# injector.net
KiCad netlist of a schematic drawn in EAGLE
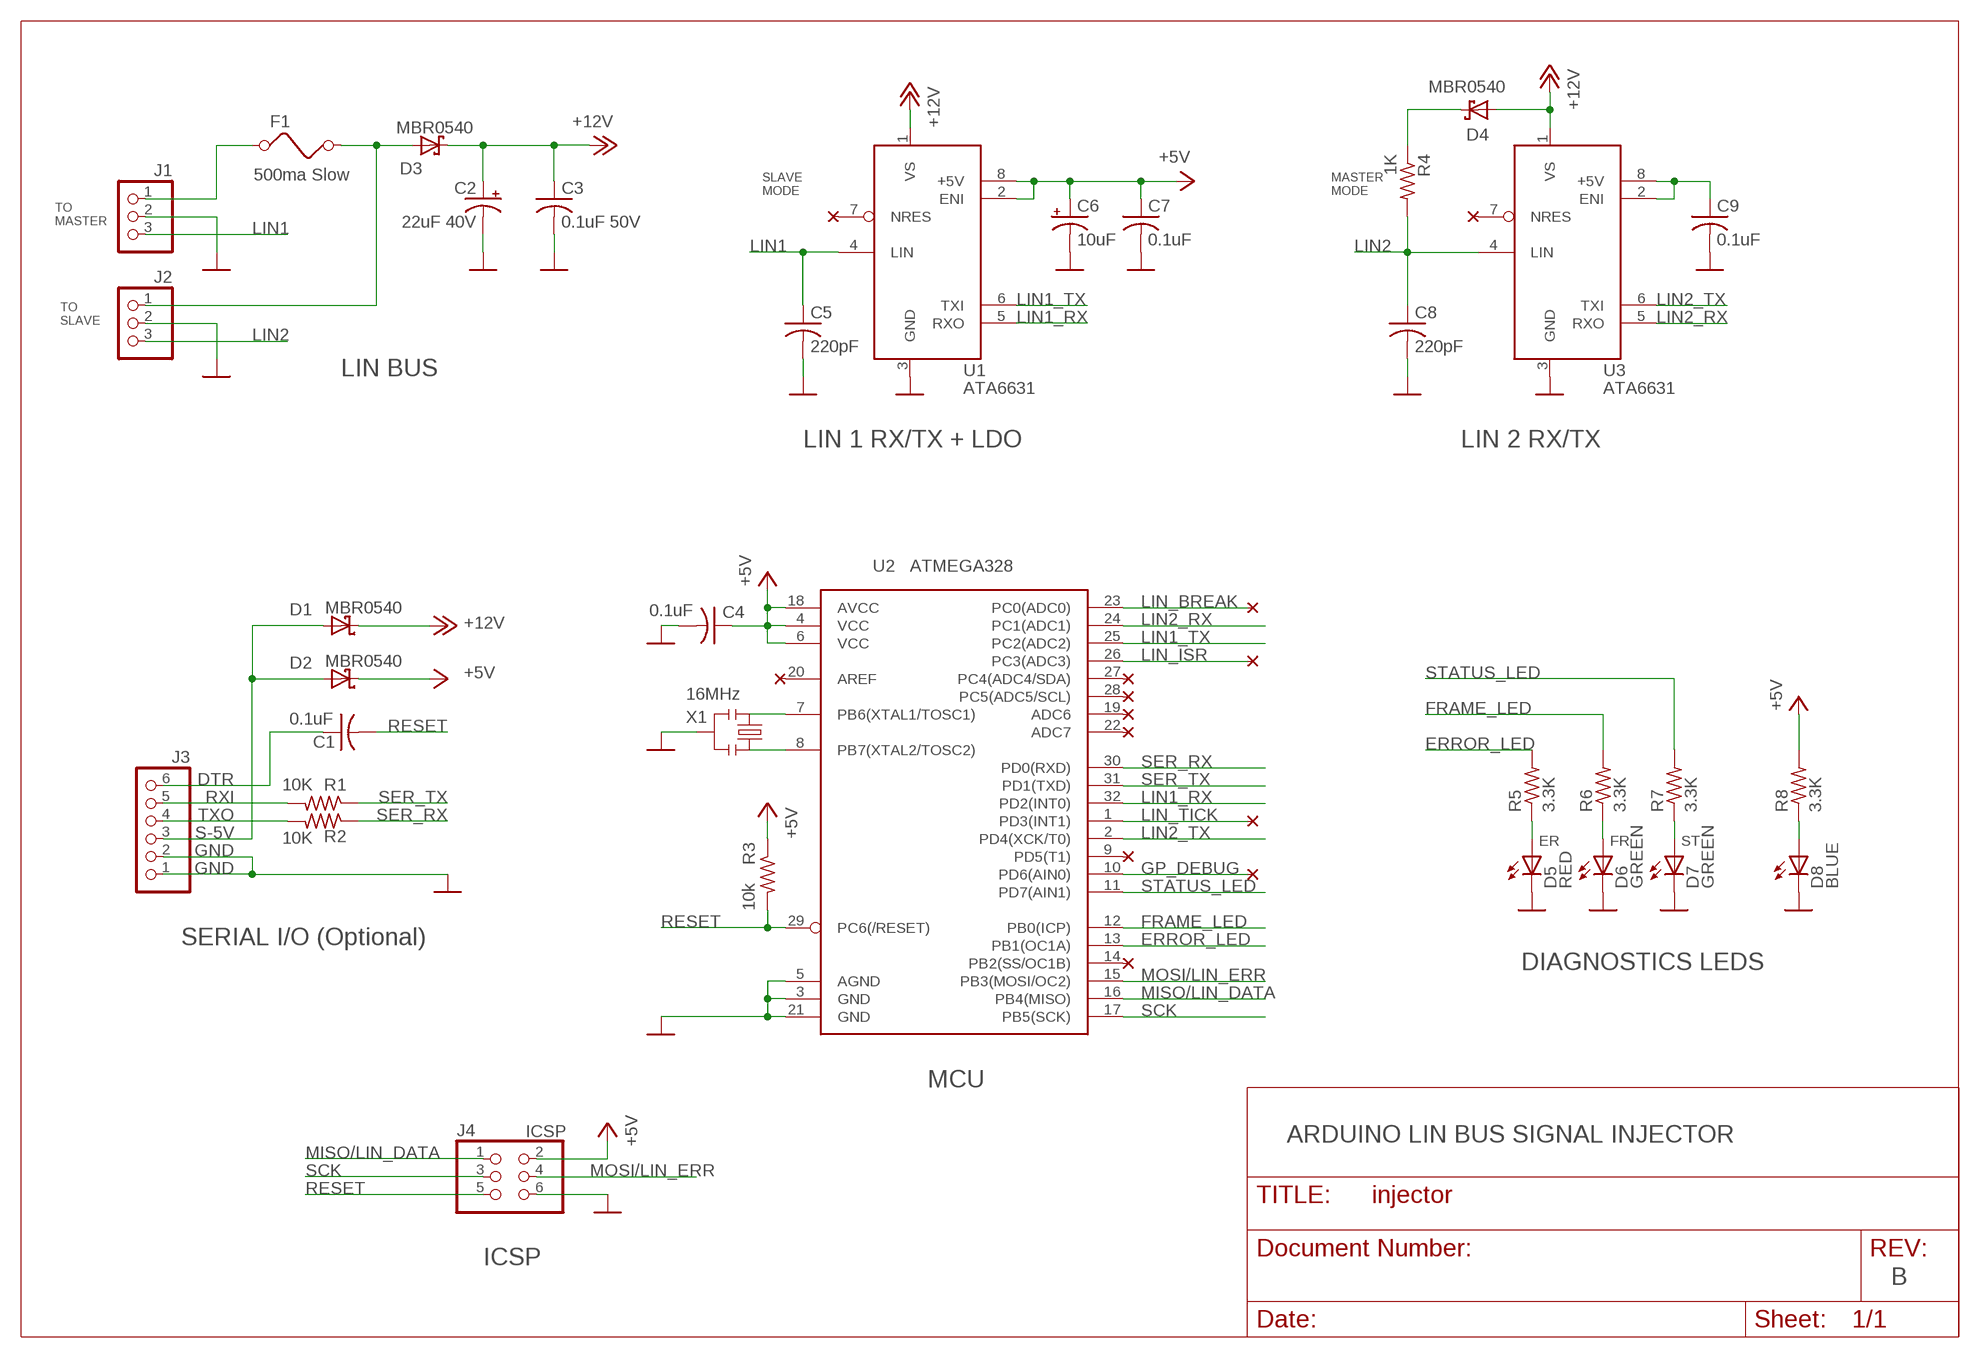
[diagram p0: schematic, sheet 1]

(export (version "E")
  (design (tool "Eeschema 10.0.6"))
  (components
    (comp (ref "C1")
      (value "0.1uF")
      (footprint "eagle-import:C0805")
      (libsource (lib "eagle-import") (part "C-USC0805"))
    )
    (comp (ref "C2")
      (value "22uF 40V")
      (footprint "eagle-import:UD-6,3X5,8_NICHICON")
      (libsource (lib "eagle-import") (part "CPOL-USUD-6,3X5,8"))
    )
    (comp (ref "C3")
      (value "0.1uF 50V")
      (footprint "eagle-import:C0805")
      (libsource (lib "eagle-import") (part "C-USC0805"))
    )
    (comp (ref "C4")
      (value "0.1uF")
      (footprint "eagle-import:C0805")
      (libsource (lib "eagle-import") (part "C-USC0805"))
    )
    (comp (ref "C5")
      (value "220pF")
      (footprint "eagle-import:C0805")
      (libsource (lib "eagle-import") (part "C-USC0805"))
    )
    (comp (ref "C6")
      (value "10uF")
      (footprint "eagle-import:A_3216-18R")
      (libsource (lib "eagle-import") (part "CPOL-USA/3216-18R"))
    )
    (comp (ref "C7")
      (value "0.1uF")
      (footprint "eagle-import:C0805")
      (libsource (lib "eagle-import") (part "C-USC0805"))
    )
    (comp (ref "C8")
      (value "220pF")
      (footprint "eagle-import:C0805")
      (libsource (lib "eagle-import") (part "C-USC0805"))
    )
    (comp (ref "C9")
      (value "0.1uF")
      (footprint "eagle-import:C0805")
      (libsource (lib "eagle-import") (part "C-USC0805"))
    )
    (comp (ref "D1")
      (value "MBR0540")
      (footprint "eagle-import:SOD123FL")
      (libsource (lib "eagle-import") (part "SMF5.0AT1"))
    )
    (comp (ref "D2")
      (value "MBR0540")
      (footprint "eagle-import:SOD123FL")
      (libsource (lib "eagle-import") (part "SMF5.0AT1"))
    )
    (comp (ref "D3")
      (value "MBR0540")
      (footprint "eagle-import:SOD123FL")
      (libsource (lib "eagle-import") (part "SMF5.0AT1"))
    )
    (comp (ref "D4")
      (value "MBR0540")
      (footprint "eagle-import:SOD123FL")
      (libsource (lib "eagle-import") (part "SMF5.0AT1"))
    )
    (comp (ref "D5")
      (value "RED")
      (footprint "eagle-import:1206-LED")
      (libsource (lib "eagle-import") (part "LED"))
    )
    (comp (ref "D6")
      (value "GREEN")
      (footprint "eagle-import:1206-LED")
      (libsource (lib "eagle-import") (part "LED"))
    )
    (comp (ref "D7")
      (value "GREEN")
      (footprint "eagle-import:1206-LED")
      (libsource (lib "eagle-import") (part "LED"))
    )
    (comp (ref "D8")
      (value "BLUE")
      (footprint "eagle-import:1206-LED")
      (libsource (lib "eagle-import") (part "LED"))
    )
    (comp (ref "F1")
      (value "500ma Slow")
      (footprint "eagle-import:1206")
      (libsource (lib "eagle-import") (part "FUSE"))
    )
    (comp (ref "J1")
      (value "PINHD-1X3")
      (footprint "eagle-import:1X03")
      (libsource (lib "eagle-import") (part "PINHD-1X3"))
    )
    (comp (ref "J2")
      (value "PINHD-1X3")
      (footprint "eagle-import:1X03")
      (libsource (lib "eagle-import") (part "PINHD-1X3"))
    )
    (comp (ref "J3")
      (value "PINHD-1X6")
      (footprint "eagle-import:1X06")
      (libsource (lib "eagle-import") (part "PINHD-1X6"))
    )
    (comp (ref "J4")
      (value "ICSP")
      (footprint "eagle-import:2X03")
      (libsource (lib "eagle-import") (part "PINHD-2X3"))
    )
    (comp (ref "R1")
      (value "10K")
      (footprint "eagle-import:R0805")
      (libsource (lib "eagle-import") (part "R-US_R0805"))
    )
    (comp (ref "R2")
      (value "10K")
      (footprint "eagle-import:R0805")
      (libsource (lib "eagle-import") (part "R-US_R0805"))
    )
    (comp (ref "R3")
      (value "10k")
      (footprint "eagle-import:R0805")
      (libsource (lib "eagle-import") (part "R-US_R0805"))
    )
    (comp (ref "R4")
      (value "1K")
      (footprint "eagle-import:R0805")
      (libsource (lib "eagle-import") (part "R-US_R0805"))
    )
    (comp (ref "R5")
      (value "3.3K")
      (footprint "eagle-import:R0805")
      (libsource (lib "eagle-import") (part "R-US_R0805"))
    )
    (comp (ref "R6")
      (value "3.3K")
      (footprint "eagle-import:R0805")
      (libsource (lib "eagle-import") (part "R-US_R0805"))
    )
    (comp (ref "R7")
      (value "3.3K")
      (footprint "eagle-import:R0805")
      (libsource (lib "eagle-import") (part "R-US_R0805"))
    )
    (comp (ref "R8")
      (value "3.3K")
      (footprint "eagle-import:R0805")
      (libsource (lib "eagle-import") (part "R-US_R0805"))
    )
    (comp (ref "U1")
      (value "ATA6631")
      (footprint "eagle-import:SO-08")
      (libsource (lib "eagle-import") (part "ATA6631"))
    )
    (comp (ref "U2")
      (value "ATMEGA328")
      (footprint "eagle-import:TQFP32-08")
      (libsource (lib "eagle-import") (part "ATMEGA328"))
    )
    (comp (ref "U3")
      (value "ATA6631")
      (footprint "eagle-import:SO-08")
      (libsource (lib "eagle-import") (part "ATA6631"))
    )
    (comp (ref "X1")
      (value "16MHz")
      (footprint "eagle-import:RESONATOR-SMD")
      (libsource (lib "eagle-import") (part "RESONATORSMD"))
    )
  )
  (nets
    (net (code "1") (name "+5V") (class "Default")
      (node (ref "C4") (pin "1") (pinfunction "1_1") (pintype "passive"))
      (node (ref "C6") (pin "+") (pinfunction "+_+") (pintype "passive"))
      (node (ref "C7") (pin "1") (pinfunction "1_1") (pintype "passive"))
      (node (ref "D2") (pin "C") (pinfunction "C_C") (pintype "passive"))
      (node (ref "J4") (pin "2") (pinfunction "2_2") (pintype "passive"))
      (node (ref "R3") (pin "1") (pinfunction "1_1") (pintype "passive"))
      (node (ref "R8") (pin "2") (pinfunction "2_2") (pintype "passive"))
      (node (ref "U1") (pin "2") (pinfunction "ENI_2") (pintype "input"))
      (node (ref "U1") (pin "8") (pinfunction "+5V_8") (pintype "power_in"))
      (node (ref "U2") (pin "18") (pinfunction "AVCC_18") (pintype "power_in"))
      (node (ref "U2") (pin "4") (pinfunction "VCC_4") (pintype "power_in"))
      (node (ref "U2") (pin "6") (pinfunction "VCC_6") (pintype "power_in"))
    )
    (net (code "2") (name "+12V") (class "Default")
      (node (ref "C2") (pin "+") (pinfunction "+_+") (pintype "passive"))
      (node (ref "C3") (pin "1") (pinfunction "1_1") (pintype "passive"))
      (node (ref "D1") (pin "C") (pinfunction "C_C") (pintype "passive"))
      (node (ref "D3") (pin "C") (pinfunction "C_C") (pintype "passive"))
      (node (ref "D4") (pin "A") (pinfunction "A_A") (pintype "passive"))
      (node (ref "U1") (pin "1") (pinfunction "VS_1") (pintype "power_in"))
      (node (ref "U3") (pin "1") (pinfunction "VS_1") (pintype "power_in"))
    )
    (net (code "3") (name "/AREF") (class "Default")
      (node (ref "U2") (pin "20") (pinfunction "AREF_20") (pintype "power_in"))
    )
    (net (code "4") (name "/DTR") (class "Default")
      (node (ref "C1") (pin "1") (pinfunction "1_1") (pintype "passive"))
      (node (ref "J3") (pin "6") (pinfunction "6_6") (pintype "passive"))
    )
    (net (code "5") (name "/ERROR_LED") (class "Default")
      (node (ref "R5") (pin "2") (pinfunction "2_2") (pintype "passive"))
      (node (ref "U2") (pin "13") (pinfunction "PB1(OC1A)_13") (pintype "bidirectional"))
    )
    (net (code "6") (name "/FRAME_LED") (class "Default")
      (node (ref "R6") (pin "2") (pinfunction "2_2") (pintype "passive"))
      (node (ref "U2") (pin "12") (pinfunction "PB0(ICP)_12") (pintype "bidirectional"))
    )
    (net (code "7") (name "/GP_DEBUG") (class "Default")
      (node (ref "U2") (pin "10") (pinfunction "PD6(AIN0)_10") (pintype "bidirectional"))
    )
    (net (code "8") (name "/LIN1") (class "Default")
      (node (ref "C5") (pin "1") (pinfunction "1_1") (pintype "passive"))
      (node (ref "J1") (pin "3") (pinfunction "3_3") (pintype "passive"))
      (node (ref "U1") (pin "4") (pinfunction "LIN_4") (pintype "bidirectional"))
    )
    (net (code "9") (name "/LIN1_RX") (class "Default")
      (node (ref "U1") (pin "5") (pinfunction "RXO_5") (pintype "output"))
      (node (ref "U2") (pin "32") (pinfunction "PD2(INT0)_32") (pintype "bidirectional"))
    )
    (net (code "10") (name "/LIN1_TX") (class "Default")
      (node (ref "U1") (pin "6") (pinfunction "TXI_6") (pintype "input"))
      (node (ref "U2") (pin "25") (pinfunction "PC2(ADC2)_25") (pintype "bidirectional"))
    )
    (net (code "11") (name "/LIN2") (class "Default")
      (node (ref "C8") (pin "1") (pinfunction "1_1") (pintype "passive"))
      (node (ref "J2") (pin "3") (pinfunction "3_3") (pintype "passive"))
      (node (ref "R4") (pin "2") (pinfunction "2_2") (pintype "passive"))
      (node (ref "U3") (pin "4") (pinfunction "LIN_4") (pintype "bidirectional"))
    )
    (net (code "12") (name "/LIN2_RX") (class "Default")
      (node (ref "U2") (pin "24") (pinfunction "PC1(ADC1)_24") (pintype "bidirectional"))
      (node (ref "U3") (pin "5") (pinfunction "RXO_5") (pintype "output"))
    )
    (net (code "13") (name "/LIN2_TX") (class "Default")
      (node (ref "U2") (pin "2") (pinfunction "PD4(XCK/T0)_2") (pintype "bidirectional"))
      (node (ref "U3") (pin "6") (pinfunction "TXI_6") (pintype "input"))
    )
    (net (code "14") (name "/LIN_BREAK") (class "Default")
      (node (ref "U2") (pin "23") (pinfunction "PC0(ADC0)_23") (pintype "bidirectional"))
    )
    (net (code "15") (name "/LIN_ISR") (class "Default")
      (node (ref "U2") (pin "26") (pinfunction "PC3(ADC3)_26") (pintype "bidirectional"))
    )
    (net (code "16") (name "/LIN_TICK") (class "Default")
      (node (ref "U2") (pin "1") (pinfunction "PD3(INT1)_1") (pintype "bidirectional"))
    )
    (net (code "17") (name "/MISO{slash}LIN_DATA") (class "Default")
      (node (ref "J4") (pin "1") (pinfunction "1_1") (pintype "passive"))
      (node (ref "U2") (pin "16") (pinfunction "PB4(MISO)_16") (pintype "bidirectional"))
    )
    (net (code "18") (name "/MOSI{slash}LIN_ERR") (class "Default")
      (node (ref "J4") (pin "4") (pinfunction "4_4") (pintype "passive"))
      (node (ref "U2") (pin "15") (pinfunction "PB3(MOSI/OC2)_15") (pintype "bidirectional"))
    )
    (net (code "19") (name "/RESET") (class "Default")
      (node (ref "C1") (pin "2") (pinfunction "2_2") (pintype "passive"))
      (node (ref "J4") (pin "5") (pinfunction "5_5") (pintype "passive"))
      (node (ref "R3") (pin "2") (pinfunction "2_2") (pintype "passive"))
      (node (ref "U2") (pin "29") (pinfunction "PC6(/RESET)_29") (pintype "bidirectional"))
    )
    (net (code "20") (name "/RXI") (class "Default")
      (node (ref "J3") (pin "5") (pinfunction "5_5") (pintype "passive"))
      (node (ref "R1") (pin "2") (pinfunction "2_2") (pintype "passive"))
    )
    (net (code "21") (name "/S-5V") (class "Default")
      (node (ref "D1") (pin "A") (pinfunction "A_A") (pintype "passive"))
      (node (ref "D2") (pin "A") (pinfunction "A_A") (pintype "passive"))
      (node (ref "J3") (pin "3") (pinfunction "3_3") (pintype "passive"))
    )
    (net (code "22") (name "/SCK") (class "Default")
      (node (ref "J4") (pin "3") (pinfunction "3_3") (pintype "passive"))
      (node (ref "U2") (pin "17") (pinfunction "PB5(SCK)_17") (pintype "bidirectional"))
    )
    (net (code "23") (name "/SER_RX") (class "Default")
      (node (ref "R2") (pin "1") (pinfunction "1_1") (pintype "passive"))
      (node (ref "U2") (pin "30") (pinfunction "PD0(RXD)_30") (pintype "bidirectional"))
    )
    (net (code "24") (name "/SER_TX") (class "Default")
      (node (ref "R1") (pin "1") (pinfunction "1_1") (pintype "passive"))
      (node (ref "U2") (pin "31") (pinfunction "PD1(TXD)_31") (pintype "bidirectional"))
    )
    (net (code "25") (name "/STATUS_LED") (class "Default")
      (node (ref "R7") (pin "2") (pinfunction "2_2") (pintype "passive"))
      (node (ref "U2") (pin "11") (pinfunction "PD7(AIN1)_11") (pintype "bidirectional"))
    )
    (net (code "26") (name "/TXO") (class "Default")
      (node (ref "J3") (pin "4") (pinfunction "4_4") (pintype "passive"))
      (node (ref "R2") (pin "2") (pinfunction "2_2") (pintype "passive"))
    )
    (net (code "27") (name "GND") (class "Default")
      (node (ref "C2") (pin "-") (pinfunction "-_-") (pintype "passive"))
      (node (ref "C3") (pin "2") (pinfunction "2_2") (pintype "passive"))
      (node (ref "C4") (pin "2") (pinfunction "2_2") (pintype "passive"))
      (node (ref "C5") (pin "2") (pinfunction "2_2") (pintype "passive"))
      (node (ref "C6") (pin "-") (pinfunction "-_-") (pintype "passive"))
      (node (ref "C7") (pin "2") (pinfunction "2_2") (pintype "passive"))
      (node (ref "C8") (pin "2") (pinfunction "2_2") (pintype "passive"))
      (node (ref "C9") (pin "2") (pinfunction "2_2") (pintype "passive"))
      (node (ref "D5") (pin "C") (pinfunction "C_C") (pintype "passive"))
      (node (ref "D6") (pin "C") (pinfunction "C_C") (pintype "passive"))
      (node (ref "D7") (pin "C") (pinfunction "C_C") (pintype "passive"))
      (node (ref "D8") (pin "C") (pinfunction "C_C") (pintype "passive"))
      (node (ref "J1") (pin "2") (pinfunction "2_2") (pintype "passive"))
      (node (ref "J2") (pin "2") (pinfunction "2_2") (pintype "passive"))
      (node (ref "J3") (pin "1") (pinfunction "1_1") (pintype "passive"))
      (node (ref "J3") (pin "2") (pinfunction "2_2") (pintype "passive"))
      (node (ref "J4") (pin "6") (pinfunction "6_6") (pintype "passive"))
      (node (ref "U1") (pin "3") (pinfunction "GND_3") (pintype "power_in"))
      (node (ref "U2") (pin "21") (pinfunction "GND_21") (pintype "power_in"))
      (node (ref "U2") (pin "3") (pinfunction "GND_3") (pintype "power_in"))
      (node (ref "U2") (pin "5") (pinfunction "AGND_5") (pintype "power_in"))
      (node (ref "U3") (pin "3") (pinfunction "GND_3") (pintype "power_in"))
      (node (ref "X1") (pin "2") (pinfunction "2_2") (pintype "passive"))
    )
    (net (code "28") (name "Net-(D3-PadA)") (class "Default")
      (node (ref "D3") (pin "A") (pinfunction "A_A") (pintype "passive"))
      (node (ref "F1") (pin "2") (pinfunction "2_2") (pintype "passive"))
      (node (ref "J2") (pin "1") (pinfunction "1_1") (pintype "passive"))
    )
    (net (code "29") (name "Net-(D4-PadC)") (class "Default")
      (node (ref "D4") (pin "C") (pinfunction "C_C") (pintype "passive"))
      (node (ref "R4") (pin "1") (pinfunction "1_1") (pintype "passive"))
    )
    (net (code "30") (name "Net-(D5-PadA)") (class "Default")
      (node (ref "D5") (pin "A") (pinfunction "A_A") (pintype "passive"))
      (node (ref "R5") (pin "1") (pinfunction "1_1") (pintype "passive"))
    )
    (net (code "31") (name "Net-(D6-PadA)") (class "Default")
      (node (ref "D6") (pin "A") (pinfunction "A_A") (pintype "passive"))
      (node (ref "R6") (pin "1") (pinfunction "1_1") (pintype "passive"))
    )
    (net (code "32") (name "Net-(D7-PadA)") (class "Default")
      (node (ref "D7") (pin "A") (pinfunction "A_A") (pintype "passive"))
      (node (ref "R7") (pin "1") (pinfunction "1_1") (pintype "passive"))
    )
    (net (code "33") (name "Net-(D8-PadA)") (class "Default")
      (node (ref "D8") (pin "A") (pinfunction "A_A") (pintype "passive"))
      (node (ref "R8") (pin "1") (pinfunction "1_1") (pintype "passive"))
    )
    (net (code "34") (name "Net-(F1-Pad1)") (class "Default")
      (node (ref "F1") (pin "1") (pinfunction "1_1") (pintype "passive"))
      (node (ref "J1") (pin "1") (pinfunction "1_1") (pintype "passive"))
    )
    (net (code "35") (name "Net-(U2-PB6(XTAL1{slash}TOSC1))") (class "Default")
      (node (ref "U2") (pin "7") (pinfunction "PB6(XTAL1/TOSC1)_7") (pintype "bidirectional"))
      (node (ref "X1") (pin "3") (pinfunction "3_3") (pintype "passive"))
    )
    (net (code "36") (name "Net-(U2-PB7(XTAL2{slash}TOSC2))") (class "Default")
      (node (ref "U2") (pin "8") (pinfunction "PB7(XTAL2/TOSC2)_8") (pintype "bidirectional"))
      (node (ref "X1") (pin "1") (pinfunction "1_1") (pintype "passive"))
    )
    (net (code "37") (name "Net-(U3-+5V)") (class "Default")
      (node (ref "C9") (pin "1") (pinfunction "1_1") (pintype "passive"))
      (node (ref "U3") (pin "2") (pinfunction "ENI_2") (pintype "input"))
      (node (ref "U3") (pin "8") (pinfunction "+5V_8") (pintype "power_in"))
    )
    (net (code "38") (name "unconnected-(U1-NRES-Pad7)") (class "Default")
      (node (ref "U1") (pin "7") (pinfunction "NRES_7") (pintype "output"))
    )
    (net (code "39") (name "unconnected-(U2-ADC6-Pad19)") (class "Default")
      (node (ref "U2") (pin "19") (pinfunction "ADC6_19") (pintype "bidirectional"))
    )
    (net (code "40") (name "unconnected-(U2-ADC7-Pad22)") (class "Default")
      (node (ref "U2") (pin "22") (pinfunction "ADC7_22") (pintype "bidirectional"))
    )
    (net (code "41") (name "unconnected-(U2-PB2(SS{slash}OC1B)-Pad14)") (class "Default")
      (node (ref "U2") (pin "14") (pinfunction "PB2(SS/OC1B)_14") (pintype "bidirectional"))
    )
    (net (code "42") (name "unconnected-(U2-PC4(ADC4{slash}SDA)-Pad27)") (class "Default")
      (node (ref "U2") (pin "27") (pinfunction "PC4(ADC4/SDA)_27") (pintype "bidirectional"))
    )
    (net (code "43") (name "unconnected-(U2-PC5(ADC5{slash}SCL)-Pad28)") (class "Default")
      (node (ref "U2") (pin "28") (pinfunction "PC5(ADC5/SCL)_28") (pintype "bidirectional"))
    )
    (net (code "44") (name "unconnected-(U2-PD5(T1)-Pad9)") (class "Default")
      (node (ref "U2") (pin "9") (pinfunction "PD5(T1)_9") (pintype "bidirectional"))
    )
    (net (code "45") (name "unconnected-(U3-NRES-Pad7)") (class "Default")
      (node (ref "U3") (pin "7") (pinfunction "NRES_7") (pintype "output"))
    )
  )
)
